# PIC18F57Q84_Curiosity_Nano_Debugger.net
KiCad netlist of a schematic drawn in Altium Designer
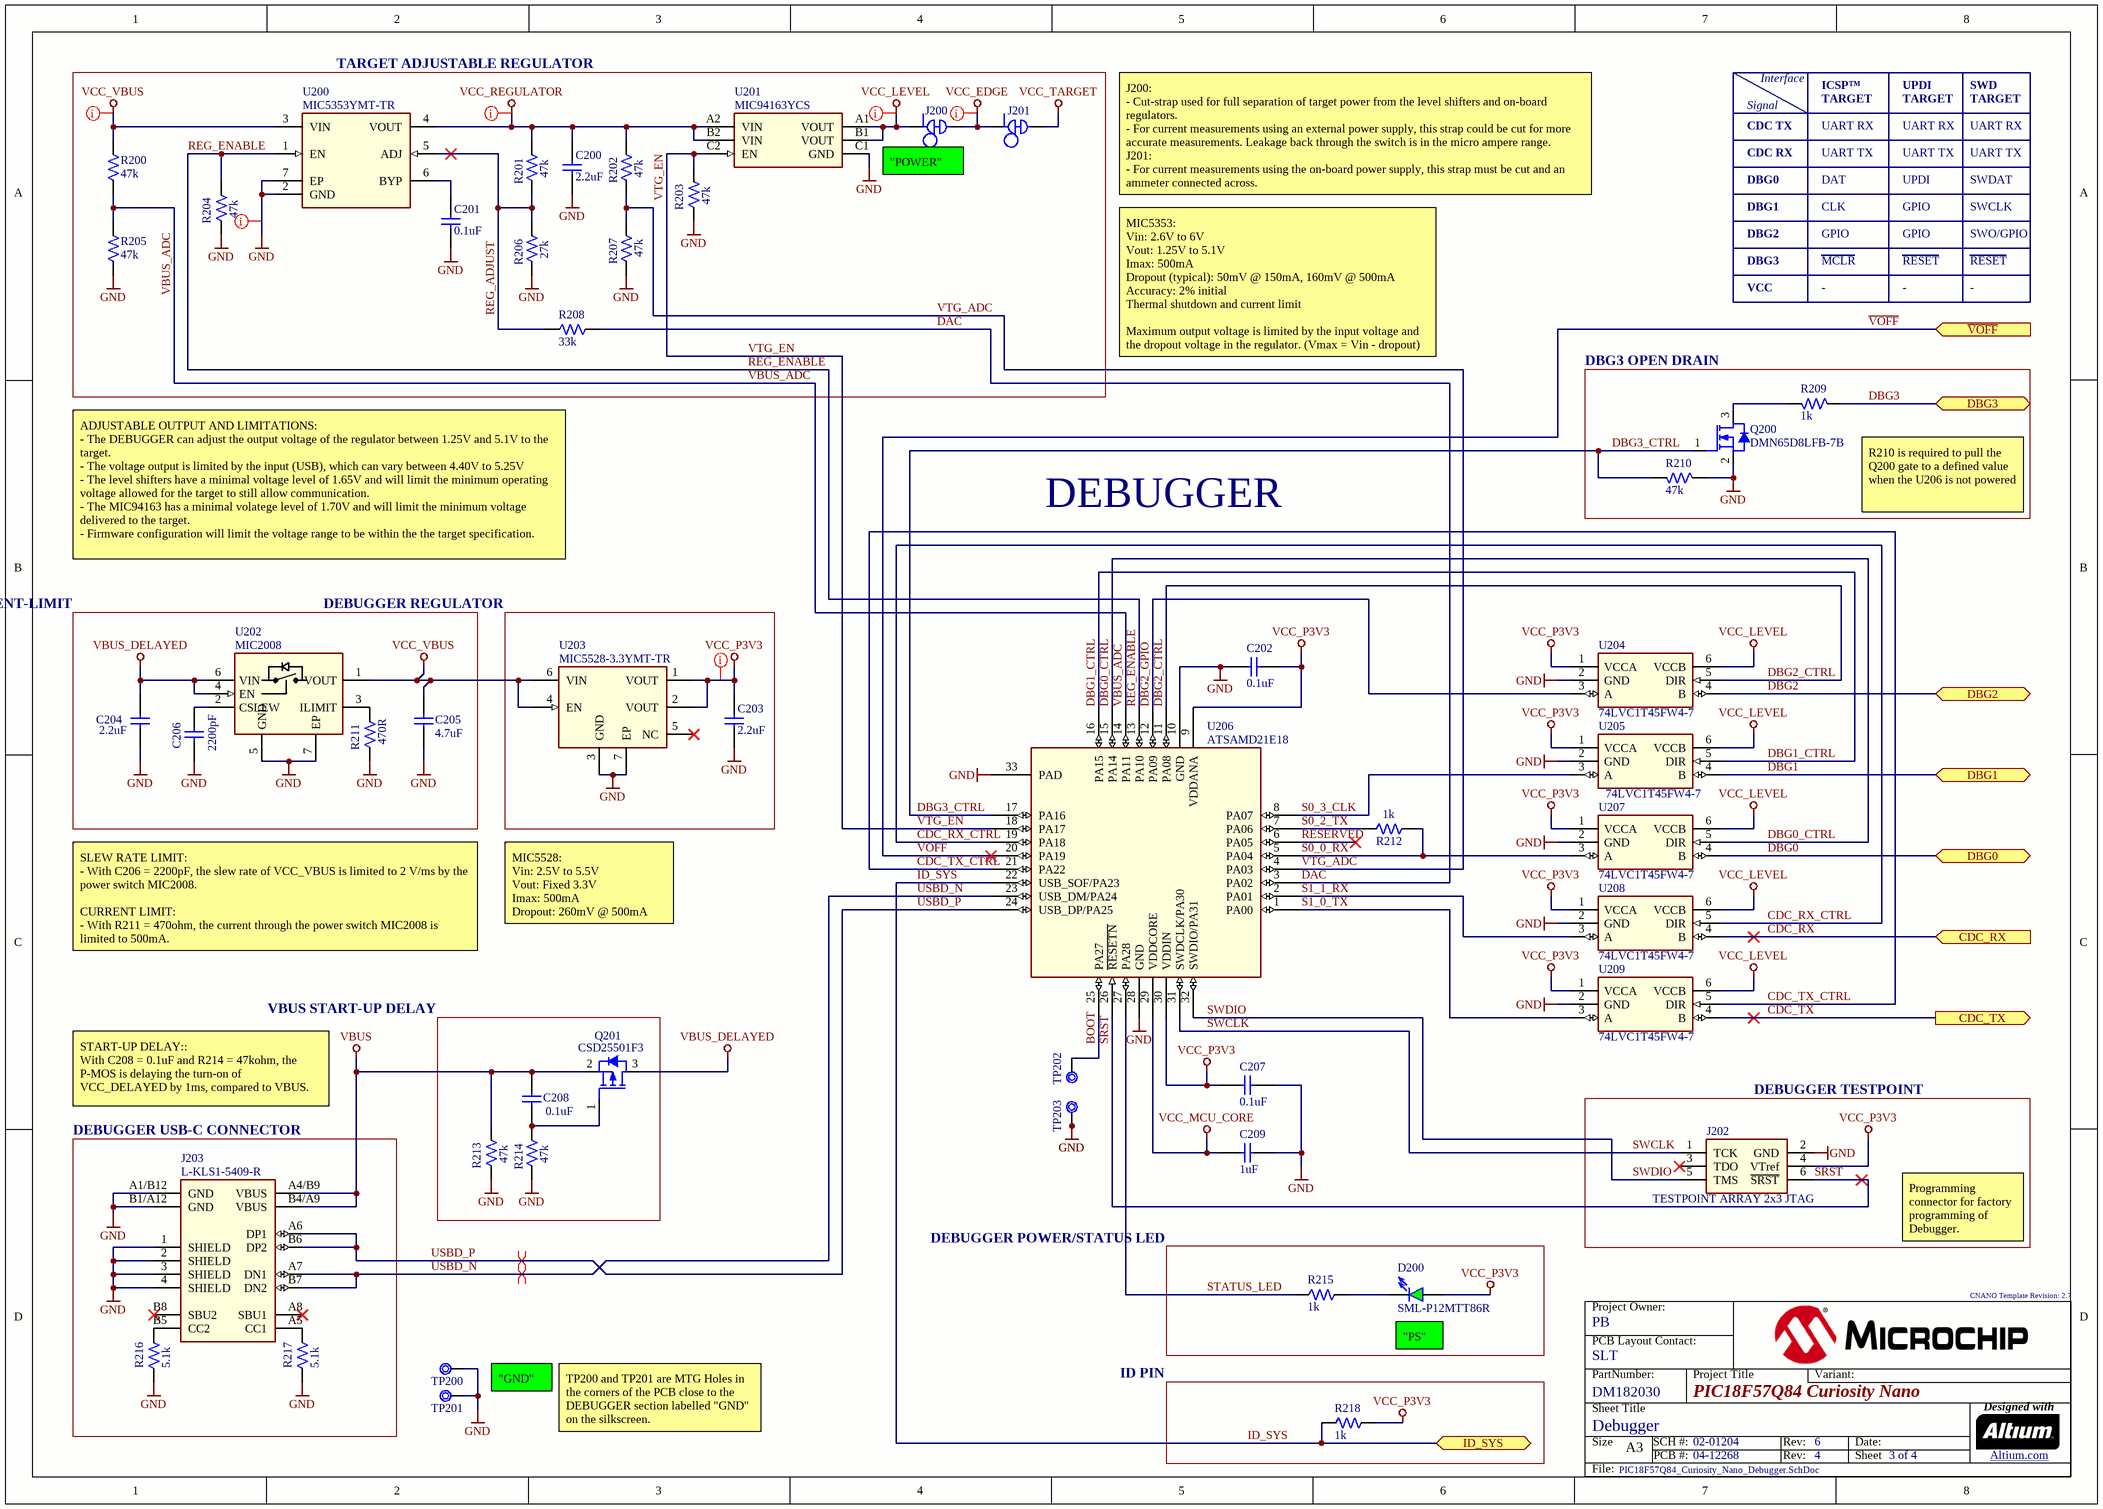
[diagram p0: PIC18F57Q84_Curiosity_Nano_Debugger.SchDoc]

(export (version "E")
  (design (tool "Eeschema 10.0.6"))
  (components
    (comp (ref "C200")
      (value "2.2uF")
      (footprint "CAP_C_0402")
      (fields
        (field (name "VOLTAGE") "10V")
        (field (name "TOLERANCE") "10%")
        (field (name "Comment") "Capacitor NP")
      )
      (libsource (lib "MCHP-CDB") (part "Capacitor NP"))
    )
    (comp (ref "C201")
      (value "0.1uF")
      (footprint "CAP_C_0402")
      (fields
        (field (name "VOLTAGE") "16V")
        (field (name "TOLERANCE") "10%")
        (field (name "Comment") "Capacitor NP")
      )
      (libsource (lib "MCHP-CDB") (part "Capacitor NP"))
    )
    (comp (ref "C202")
      (value "0.1uF")
      (footprint "CAP_C_0402")
      (fields
        (field (name "VOLTAGE") "16V")
        (field (name "TOLERANCE") "10%")
        (field (name "Comment") "Capacitor NP")
      )
      (libsource (lib "MCHP-CDB") (part "Capacitor NP"))
    )
    (comp (ref "C203")
      (value "2.2uF")
      (footprint "CAP_C_0402")
      (fields
        (field (name "VOLTAGE") "10V")
        (field (name "TOLERANCE") "10%")
        (field (name "Comment") "Capacitor NP")
      )
      (libsource (lib "MCHP-CDB") (part "Capacitor NP"))
    )
    (comp (ref "C204")
      (value "2.2uF")
      (footprint "CAP_C_0402")
      (fields
        (field (name "VOLTAGE") "10V")
        (field (name "TOLERANCE") "10%")
        (field (name "Comment") "Capacitor NP")
      )
      (libsource (lib "MCHP-CDB") (part "Capacitor NP"))
    )
    (comp (ref "C205")
      (value "4.7uF")
      (footprint "CAP_C_0603")
      (fields
        (field (name "VOLTAGE") "10V")
        (field (name "TOLERANCE") "10%")
        (field (name "Comment") "Capacitor NP")
      )
      (libsource (lib "MCHP-CDB") (part "Capacitor NP"))
    )
    (comp (ref "C206")
      (value "2200pF")
      (footprint "CAP_C_0402")
      (fields
        (field (name "VOLTAGE") "25V")
        (field (name "TOLERANCE") "5%")
        (field (name "Comment") "Capacitor NP")
      )
      (libsource (lib "MCHP-CDB") (part "Capacitor NP"))
    )
    (comp (ref "C207")
      (value "0.1uF")
      (footprint "CAP_C_0402")
      (fields
        (field (name "VOLTAGE") "16V")
        (field (name "TOLERANCE") "10%")
        (field (name "Comment") "Capacitor NP")
      )
      (libsource (lib "MCHP-CDB") (part "Capacitor NP"))
    )
    (comp (ref "C208")
      (value "0.1uF")
      (footprint "CAP_C_0402")
      (fields
        (field (name "VOLTAGE") "16V")
        (field (name "TOLERANCE") "10%")
        (field (name "Comment") "Capacitor NP")
      )
      (libsource (lib "MCHP-CDB") (part "Capacitor NP"))
    )
    (comp (ref "C209")
      (value "1uF")
      (footprint "CAP_C_0402")
      (fields
        (field (name "VOLTAGE") "6.3V")
        (field (name "TOLERANCE") "10%")
        (field (name "Comment") "Capacitor NP")
      )
      (libsource (lib "MCHP-CDB") (part "Capacitor NP"))
    )
    (comp (ref "D200")
      (value "LED_green")
      (footprint "LED_0402_GREEN")
      (description "LED")
      (fields (field (name "POWER") "54mW") (field (name "MANUFACTURER PART NUMBER 1") "SML-P12MTT86R"))
      (libsource (lib "MCHP-CDB") (part "LED_green"))
    )
    (comp (ref "J200")
      (value "CON JMPR LINK CLOSED")
      (footprint "CON_JMPR_0402_PCB_TRACE_LINK")
      (libsource (lib "MCHP-CDB") (part "CON JMPR LINK CLOSED"))
    )
    (comp (ref "J201")
      (value "CON JMPR LINK CLOSED")
      (footprint "CON_JMPR_2.54_1x2_TH_PCB_TRACE_LINK")
      (libsource (lib "MCHP-CDB") (part "CON JMPR LINK CLOSED"))
    )
    (comp (ref "J202")
      (value "TESTPOINT ARRAY 2x3 JTAG")
      (footprint "TESTPOINT_ARRAY_2x3_1.27mm_pitch_SMD")
      (fields (field (name "Comment") "TP ARRAY NO BOM"))
      (libsource (lib "MCHP-CDB") (part "TESTPOINT ARRAY 2x3 JTAG"))
    )
    (comp (ref "J203")
      (value "CON USB2.0-C RCPT SMD RA KLS KLS1-5409")
      (footprint "CON_USB2.0-C_RCPT_SMD_RA_KLS_KLS1-5409")
      (fields (field (name "VOLTAGE") "100V AC") (field (name "MANUFACTURER PART NUMBER 1") "L-KLS1-5409-R"))
      (libsource (lib "MCHP-CDB") (part "CON USB2.0-C RCPT SMD RA KLS KLS1-5409"))
    )
    (comp (ref "Q200")
      (value "DMN65D8LFB-7B")
      (footprint "X1-DFN1006-3")
      (description "Transistor MOS")
      (fields (field (name "POWER") "430mW") (field (name "VOLTAGE") "60V"))
      (libsource (lib "MCHP-CDB") (part "Transistor MOS-N GSD"))
    )
    (comp (ref "Q201")
      (value "CSD25501F3")
      (footprint "LGA-3_GSD_0.7x0.6_CSD25501F3")
      (description "Transistor MOS")
      (fields (field (name "VOLTAGE") "-20V") (field (name "Comment") "Transistor MOS-P GSD"))
      (libsource (lib "MCHP-CDB") (part "Transistor MOS-P GSD"))
    )
    (comp (ref "R200")
      (value "47k")
      (footprint "RES_C_0402")
      (description "Resistor")
      (fields (field (name "TOLERANCE") "1%") (field (name "VOLTAGE") "50V"))
      (libsource (lib "MCHP-CDB") (part "Resistor"))
    )
    (comp (ref "R201")
      (value "47k")
      (footprint "RES_C_0402")
      (description "Resistor")
      (fields (field (name "TOLERANCE") "1%") (field (name "VOLTAGE") "50V"))
      (libsource (lib "MCHP-CDB") (part "Resistor"))
    )
    (comp (ref "R202")
      (value "47k")
      (footprint "RES_C_0402")
      (description "Resistor")
      (fields (field (name "TOLERANCE") "1%") (field (name "VOLTAGE") "50V"))
      (libsource (lib "MCHP-CDB") (part "Resistor"))
    )
    (comp (ref "R203")
      (value "47k")
      (footprint "RES_C_0402")
      (description "Resistor")
      (fields (field (name "TOLERANCE") "1%") (field (name "VOLTAGE") "50V"))
      (libsource (lib "MCHP-CDB") (part "Resistor"))
    )
    (comp (ref "R204")
      (value "47k")
      (footprint "RES_C_0402")
      (description "Resistor")
      (fields (field (name "TOLERANCE") "1%") (field (name "VOLTAGE") "50V"))
      (libsource (lib "MCHP-CDB") (part "Resistor"))
    )
    (comp (ref "R205")
      (value "47k")
      (footprint "RES_C_0402")
      (description "Resistor")
      (fields (field (name "TOLERANCE") "1%") (field (name "VOLTAGE") "50V"))
      (libsource (lib "MCHP-CDB") (part "Resistor"))
    )
    (comp (ref "R206")
      (value "27k")
      (footprint "RES_C_0402")
      (description "Resistor")
      (fields (field (name "TOLERANCE") "1%") (field (name "VOLTAGE") "50V"))
      (libsource (lib "MCHP-CDB") (part "Resistor"))
    )
    (comp (ref "R207")
      (value "47k")
      (footprint "RES_C_0402")
      (description "Resistor")
      (fields (field (name "TOLERANCE") "1%") (field (name "VOLTAGE") "50V"))
      (libsource (lib "MCHP-CDB") (part "Resistor"))
    )
    (comp (ref "R208")
      (value "33k")
      (footprint "RES_C_0402")
      (description "Resistor")
      (fields (field (name "TOLERANCE") "1%") (field (name "POWER") "1/16W"))
      (libsource (lib "MCHP-CDB") (part "Resistor"))
    )
    (comp (ref "R209")
      (value "1k")
      (footprint "RES_C_0402")
      (description "Resistor")
      (fields (field (name "TOLERANCE") "1%") (field (name "VOLTAGE") "50V"))
      (libsource (lib "MCHP-CDB") (part "Resistor"))
    )
    (comp (ref "R210")
      (value "47k")
      (footprint "RES_C_0402")
      (description "Resistor")
      (fields (field (name "TOLERANCE") "1%") (field (name "VOLTAGE") "50V"))
      (libsource (lib "MCHP-CDB") (part "Resistor"))
    )
    (comp (ref "R211")
      (value "470R")
      (footprint "RES_C_0402")
      (description "Resistor")
      (fields (field (name "TOLERANCE") "1%"))
      (libsource (lib "") (part "Resistor_1"))
    )
    (comp (ref "R212")
      (value "1k")
      (footprint "RES_C_0402")
      (description "Resistor")
      (fields (field (name "TOLERANCE") "1%") (field (name "VOLTAGE") "50V"))
      (libsource (lib "MCHP-CDB") (part "Resistor"))
    )
    (comp (ref "R213")
      (value "47k")
      (footprint "RES_C_0402")
      (description "Resistor")
      (fields (field (name "TOLERANCE") "1%") (field (name "VOLTAGE") "50V"))
      (libsource (lib "MCHP-CDB") (part "Resistor"))
    )
    (comp (ref "R214")
      (value "47k")
      (footprint "RES_C_0402")
      (description "Resistor")
      (fields (field (name "TOLERANCE") "1%") (field (name "VOLTAGE") "50V"))
      (libsource (lib "") (part "Resistor_1"))
    )
    (comp (ref "R215")
      (value "1k")
      (footprint "RES_C_0402")
      (description "Resistor")
      (fields (field (name "TOLERANCE") "1%") (field (name "VOLTAGE") "50V"))
      (libsource (lib "MCHP-CDB") (part "Resistor"))
    )
    (comp (ref "R216")
      (value "5.1k")
      (footprint "RES_C_0402")
      (description "Resistor")
      (fields (field (name "TOLERANCE") "1%") (field (name "POWER") "1/10W"))
      (libsource (lib "") (part "Resistor_1"))
    )
    (comp (ref "R217")
      (value "5.1k")
      (footprint "RES_C_0402")
      (description "Resistor")
      (fields (field (name "TOLERANCE") "1%") (field (name "POWER") "1/10W"))
      (libsource (lib "") (part "Resistor_1"))
    )
    (comp (ref "R218")
      (value "1k")
      (footprint "RES_C_0402")
      (description "Resistor")
      (fields (field (name "TOLERANCE") "1%") (field (name "VOLTAGE") "50V"))
      (libsource (lib "MCHP-CDB") (part "Resistor"))
    )
    (comp (ref "TP200")
      (value "Test Point No BOM")
      (footprint "TP_3.6X2.7")
      (description "Test Point")
      (libsource (lib "MCHP-CDB") (part "Test Point No BOM"))
    )
    (comp (ref "TP201")
      (value "Test Point No BOM")
      (footprint "TP_3.6X2.7")
      (description "Test Point")
      (libsource (lib "MCHP-CDB") (part "Test Point No BOM"))
    )
    (comp (ref "TP202")
      (value "Test Point No BOM")
      (footprint "CON_TP_0.8dia_SMD_with_Test_Jig_Layer")
      (description "Test Point")
      (libsource (lib "MCHP-CDB") (part "Test Point No BOM"))
    )
    (comp (ref "TP203")
      (value "Test Point No BOM")
      (footprint "CON_TP_0.8dia_SMD_with_Test_Jig_Layer")
      (description "Test Point")
      (libsource (lib "MCHP-CDB") (part "Test Point No BOM"))
    )
    (comp (ref "U200")
      (value "MIC5353YMT-TR")
      (footprint "MLF-6 1.6X1.6mm")
      (description "LDO Regulator")
      (fields (field (name "Comment") "MIC53XX ADJ MLF-6"))
      (libsource (lib "MCHP-CDB") (part "MIC53XX ADJ MLF-6"))
    )
    (comp (ref "U201")
      (value "MIC94163YCS")
      (footprint "MIC94163_1.5MM_1MM")
      (fields (field (name "Comment") "MIC94163_1.5MM_1MM"))
      (libsource (lib "MCHP-CDB") (part "MIC94163_1.5MM_1MM"))
    )
    (comp (ref "U202")
      (value "MIC2008")
      (footprint "VDFN-6_2x2_EP0.8X1.40")
      (fields (field (name "Comment") "MIC2008YML-TR VDFN-6"))
      (libsource (lib "MCHP-CDB") (part "MIC2008YML-TR VDFN-6"))
    )
    (comp (ref "U203")
      (value "MIC5528MT DFN-6")
      (footprint "DFN-6_1.2x1.2")
      (fields (field (name "MANUFACTURER PART NUMBER 1") "MIC5528-3.3YMT-TR"))
      (libsource (lib "MCHP-CDB") (part "MIC5528MT DFN-6"))
    )
    (comp (ref "U204")
      (value "74LVC1T45FW4-7")
      (footprint "X2-DFN1010-6")
      (fields (field (name "Comment") "74LVC(H)1T45 SOT-23-6_SC-70-6_SOT-6_SOT-363_DSBGA"))
      (libsource (lib "MCHP-CDB") (part "74LVC(H)1T45 SOT-23-6_SC-70-6_SOT-6_SOT-363_DSBGA"))
    )
    (comp (ref "U205")
      (value "74LVC1T45FW4-7")
      (footprint "X2-DFN1010-6")
      (fields (field (name "Comment") "74LVC(H)1T45 SOT-23-6_SC-70-6_SOT-6_SOT-363_DSBGA"))
      (libsource (lib "MCHP-CDB") (part "74LVC(H)1T45 SOT-23-6_SC-70-6_SOT-6_SOT-363_DSBGA"))
    )
    (comp (ref "U206")
      (value "ATSAMD21E18")
      (footprint "QFN-32_5X5_EP3.6x3.6_L")
      (fields (field (name "Comment") "SAMD21E QFN-32"))
      (libsource (lib "MCHP-CDB") (part "SAMD21E QFN-32"))
    )
    (comp (ref "U207")
      (value "74LVC1T45FW4-7")
      (footprint "X2-DFN1010-6")
      (fields (field (name "Comment") "74LVC(H)1T45 SOT-23-6_SC-70-6_SOT-6_SOT-363_DSBGA"))
      (libsource (lib "MCHP-CDB") (part "74LVC(H)1T45 SOT-23-6_SC-70-6_SOT-6_SOT-363_DSBGA"))
    )
    (comp (ref "U208")
      (value "74LVC1T45FW4-7")
      (footprint "X2-DFN1010-6")
      (fields (field (name "Comment") "74LVC(H)1T45 SOT-23-6_SC-70-6_SOT-6_SOT-363_DSBGA"))
      (libsource (lib "MCHP-CDB") (part "74LVC(H)1T45 SOT-23-6_SC-70-6_SOT-6_SOT-363_DSBGA"))
    )
    (comp (ref "U209")
      (value "74LVC1T45FW4-7")
      (footprint "X2-DFN1010-6")
      (fields (field (name "Comment") "74LVC(H)1T45 SOT-23-6_SC-70-6_SOT-6_SOT-363_DSBGA"))
      (libsource (lib "MCHP-CDB") (part "74LVC(H)1T45 SOT-23-6_SC-70-6_SOT-6_SOT-363_DSBGA"))
    )
  )
  (nets
    (net (code "1") (name "/BOOT") (class "Default")
      (node (ref "TP202") (pin "1") (pinfunction "1_1") (pintype "passive"))
      (node (ref "U206") (pin "25") (pinfunction "PA27_25") (pintype "bidirectional"))
    )
    (net (code "2") (name "/CDC_RX") (class "Default")
      (node (ref "U208") (pin "4") (pinfunction "B_4") (pintype "bidirectional"))
    )
    (net (code "3") (name "/CDC_RX_CTRL") (class "Default")
      (node (ref "U206") (pin "19") (pinfunction "PA18_19") (pintype "bidirectional"))
      (node (ref "U208") (pin "5") (pinfunction "DIR_5") (pintype "input"))
    )
    (net (code "4") (name "/CDC_TX") (class "Default")
      (node (ref "U209") (pin "4") (pinfunction "B_4") (pintype "bidirectional"))
    )
    (net (code "5") (name "/CDC_TX_CTRL") (class "Default")
      (node (ref "U206") (pin "21") (pinfunction "PA22_21") (pintype "bidirectional"))
      (node (ref "U209") (pin "5") (pinfunction "DIR_5") (pintype "input"))
    )
    (net (code "6") (name "/DAC") (class "Default")
      (node (ref "R208") (pin "2") (pinfunction "2_2") (pintype "passive"))
      (node (ref "U206") (pin "3") (pinfunction "PA02_3") (pintype "bidirectional"))
    )
    (net (code "7") (name "/DBG0") (class "Default")
      (node (ref "U207") (pin "4") (pinfunction "B_4") (pintype "bidirectional"))
    )
    (net (code "8") (name "/DBG0_CTRL") (class "Default")
      (node (ref "U206") (pin "15") (pinfunction "PA14_15") (pintype "bidirectional"))
      (node (ref "U207") (pin "5") (pinfunction "DIR_5") (pintype "input"))
    )
    (net (code "9") (name "/DBG1") (class "Default")
      (node (ref "U205") (pin "4") (pinfunction "B_4") (pintype "bidirectional"))
    )
    (net (code "10") (name "/DBG1_CTRL") (class "Default")
      (node (ref "U205") (pin "5") (pinfunction "DIR_5") (pintype "input"))
      (node (ref "U206") (pin "16") (pinfunction "PA15_16") (pintype "bidirectional"))
    )
    (net (code "11") (name "/DBG2") (class "Default")
      (node (ref "U204") (pin "4") (pinfunction "B_4") (pintype "bidirectional"))
    )
    (net (code "12") (name "/DBG2_CTRL") (class "Default")
      (node (ref "U204") (pin "5") (pinfunction "DIR_5") (pintype "input"))
      (node (ref "U206") (pin "11") (pinfunction "PA08_11") (pintype "bidirectional"))
    )
    (net (code "13") (name "/DBG2_GPIO") (class "Default")
      (node (ref "U204") (pin "3") (pinfunction "A_3") (pintype "bidirectional"))
      (node (ref "U206") (pin "12") (pinfunction "PA09_12") (pintype "bidirectional"))
    )
    (net (code "14") (name "/DBG3") (class "Default")
      (node (ref "R209") (pin "2") (pinfunction "2_2") (pintype "passive"))
    )
    (net (code "15") (name "/DBG3_CTRL") (class "Default")
      (node (ref "Q200") (pin "1") (pinfunction "G_1") (pintype "passive"))
      (node (ref "R210") (pin "1") (pinfunction "1_1") (pintype "passive"))
      (node (ref "U206") (pin "17") (pinfunction "PA16_17") (pintype "bidirectional"))
    )
    (net (code "16") (name "/ID_SYS") (class "Default")
      (node (ref "R218") (pin "1") (pinfunction "1_1") (pintype "passive"))
      (node (ref "U206") (pin "22") (pinfunction "USB_SOF/PA23_22") (pintype "bidirectional"))
    )
    (net (code "17") (name "/REG_ADJUST") (class "Default")
      (node (ref "R201") (pin "2") (pinfunction "2_2") (pintype "passive"))
      (node (ref "R206") (pin "2") (pinfunction "2_2") (pintype "passive"))
      (node (ref "R208") (pin "1") (pinfunction "1_1") (pintype "passive"))
      (node (ref "U200") (pin "5") (pinfunction "ADJ_5") (pintype "input"))
    )
    (net (code "18") (name "/REG_ENABLE") (class "Default")
      (node (ref "R204") (pin "1") (pinfunction "1_1") (pintype "passive"))
      (node (ref "U200") (pin "1") (pinfunction "EN_1") (pintype "input"))
      (node (ref "U206") (pin "13") (pinfunction "PA10_13") (pintype "bidirectional"))
    )
    (net (code "19") (name "/RESERVED") (class "Default")
      (node (ref "U206") (pin "6") (pinfunction "PA05_6") (pintype "bidirectional+no_connect"))
    )
    (net (code "20") (name "/S0_0_RX") (class "Default")
      (node (ref "R212") (pin "1") (pinfunction "1_1") (pintype "passive"))
      (node (ref "U206") (pin "5") (pinfunction "PA04_5") (pintype "bidirectional"))
      (node (ref "U207") (pin "3") (pinfunction "A_3") (pintype "bidirectional"))
    )
    (net (code "21") (name "/S0_2_TX") (class "Default")
      (node (ref "R212") (pin "2") (pinfunction "2_2") (pintype "passive"))
      (node (ref "U206") (pin "7") (pinfunction "PA06_7") (pintype "bidirectional"))
    )
    (net (code "22") (name "/S0_3_CLK") (class "Default")
      (node (ref "U205") (pin "3") (pinfunction "A_3") (pintype "bidirectional"))
      (node (ref "U206") (pin "8") (pinfunction "PA07_8") (pintype "bidirectional"))
    )
    (net (code "23") (name "/S1_0_TX") (class "Default")
      (node (ref "U206") (pin "1") (pinfunction "PA00_1") (pintype "bidirectional"))
      (node (ref "U209") (pin "3") (pinfunction "A_3") (pintype "bidirectional"))
    )
    (net (code "24") (name "/S1_1_RX") (class "Default")
      (node (ref "U206") (pin "2") (pinfunction "PA01_2") (pintype "bidirectional"))
      (node (ref "U208") (pin "3") (pinfunction "A_3") (pintype "bidirectional"))
    )
    (net (code "25") (name "/STATUS_LED") (class "Default")
      (node (ref "R215") (pin "2") (pinfunction "2_2") (pintype "passive"))
      (node (ref "U206") (pin "27") (pinfunction "PA28_27") (pintype "bidirectional"))
    )
    (net (code "26") (name "/SWCLK") (class "Default")
      (node (ref "J202") (pin "1") (pinfunction "TCK_1") (pintype "passive"))
      (node (ref "U206") (pin "31") (pinfunction "SWDCLK/PA30_31") (pintype "bidirectional"))
    )
    (net (code "27") (name "/SWDIO") (class "Default")
      (node (ref "J202") (pin "5") (pinfunction "TMS_5") (pintype "passive"))
      (node (ref "U206") (pin "32") (pinfunction "SWDIO/PA31_32") (pintype "bidirectional"))
    )
    (net (code "28") (name "/USBD_N") (class "Default")
      (node (ref "J203") (pin "A7") (pinfunction "DN1_A7") (pintype "bidirectional"))
      (node (ref "J203") (pin "B7") (pinfunction "DN2_B7") (pintype "bidirectional"))
      (node (ref "U206") (pin "23") (pinfunction "USB_DM/PA24_23") (pintype "bidirectional"))
    )
    (net (code "29") (name "/USBD_P") (class "Default")
      (node (ref "J203") (pin "A6") (pinfunction "DP1_A6") (pintype "bidirectional"))
      (node (ref "J203") (pin "B6") (pinfunction "DP2_B6") (pintype "bidirectional"))
      (node (ref "U206") (pin "24") (pinfunction "USB_DP/PA25_24") (pintype "bidirectional"))
    )
    (net (code "30") (name "/VBUS_ADC") (class "Default")
      (node (ref "R200") (pin "2") (pinfunction "2_2") (pintype "passive"))
      (node (ref "R205") (pin "2") (pinfunction "2_2") (pintype "passive"))
      (node (ref "U206") (pin "14") (pinfunction "PA11_14") (pintype "bidirectional"))
    )
    (net (code "31") (name "/VTG_ADC") (class "Default")
      (node (ref "R202") (pin "1") (pinfunction "1_1") (pintype "passive"))
      (node (ref "R207") (pin "2") (pinfunction "2_2") (pintype "passive"))
      (node (ref "U206") (pin "4") (pinfunction "PA03_4") (pintype "bidirectional"))
    )
    (net (code "32") (name "/VTG_EN") (class "Default")
      (node (ref "R203") (pin "1") (pinfunction "1_1") (pintype "passive"))
      (node (ref "U201") (pin "C2") (pinfunction "EN_C2") (pintype "input"))
      (node (ref "U206") (pin "18") (pinfunction "PA17_18") (pintype "bidirectional"))
    )
    (net (code "33") (name "/~{SRST}") (class "Default")
      (node (ref "J202") (pin "6") (pinfunction "~{SRST}_6") (pintype "passive"))
      (node (ref "U206") (pin "26") (pinfunction "~{RESETN}_26") (pintype "input"))
    )
    (net (code "34") (name "/~{VOFF}") (class "Default")
      (node (ref "U206") (pin "20") (pinfunction "PA19_20") (pintype "bidirectional+no_connect"))
    )
    (net (code "35") (name "GND") (class "Default")
      (node (ref "C200") (pin "1") (pinfunction "1_1") (pintype "passive"))
      (node (ref "C201") (pin "2") (pinfunction "2_2") (pintype "passive"))
      (node (ref "C202") (pin "1") (pinfunction "1_1") (pintype "passive"))
      (node (ref "C203") (pin "1") (pinfunction "1_1") (pintype "passive"))
      (node (ref "C204") (pin "1") (pinfunction "1_1") (pintype "passive"))
      (node (ref "C205") (pin "1") (pinfunction "1_1") (pintype "passive"))
      (node (ref "C206") (pin "1") (pinfunction "1_1") (pintype "passive"))
      (node (ref "C207") (pin "2") (pinfunction "2_2") (pintype "passive"))
      (node (ref "C209") (pin "1") (pinfunction "1_1") (pintype "passive"))
      (node (ref "J202") (pin "2") (pinfunction "GND_2") (pintype "power_in"))
      (node (ref "J203") (pin "1") (pinfunction "SHIELD_1") (pintype "passive"))
      (node (ref "J203") (pin "2") (pinfunction "SHIELD_2") (pintype "passive"))
      (node (ref "J203") (pin "3") (pinfunction "SHIELD_3") (pintype "passive"))
      (node (ref "J203") (pin "4") (pinfunction "SHIELD_4") (pintype "passive"))
      (node (ref "J203") (pin "A1/B12") (pinfunction "GND_A1/B12") (pintype "power_in"))
      (node (ref "J203") (pin "B1/A12") (pinfunction "GND_B1/A12") (pintype "power_in"))
      (node (ref "Q200") (pin "2") (pinfunction "S_2") (pintype "passive"))
      (node (ref "R203") (pin "2") (pinfunction "2_2") (pintype "passive"))
      (node (ref "R204") (pin "2") (pinfunction "2_2") (pintype "passive"))
      (node (ref "R205") (pin "1") (pinfunction "1_1") (pintype "passive"))
      (node (ref "R206") (pin "1") (pinfunction "1_1") (pintype "passive"))
      (node (ref "R207") (pin "1") (pinfunction "1_1") (pintype "passive"))
      (node (ref "R210") (pin "2") (pinfunction "2_2") (pintype "passive"))
      (node (ref "R211") (pin "2") (pinfunction "2_2") (pintype "passive"))
      (node (ref "R213") (pin "2") (pinfunction "2_2") (pintype "passive"))
      (node (ref "R214") (pin "2") (pinfunction "2_2") (pintype "passive"))
      (node (ref "R216") (pin "2") (pinfunction "2_2") (pintype "passive"))
      (node (ref "R217") (pin "2") (pinfunction "2_2") (pintype "passive"))
      (node (ref "TP200") (pin "1") (pinfunction "1_1") (pintype "passive"))
      (node (ref "TP201") (pin "1") (pinfunction "1_1") (pintype "passive"))
      (node (ref "TP203") (pin "1") (pinfunction "1_1") (pintype "passive"))
      (node (ref "U200") (pin "2") (pinfunction "GND_2") (pintype "power_in"))
      (node (ref "U200") (pin "7") (pinfunction "EP_7") (pintype "passive"))
      (node (ref "U201") (pin "C1") (pinfunction "GND_C1") (pintype "passive"))
      (node (ref "U202") (pin "5") (pinfunction "GND_5") (pintype "power_in"))
      (node (ref "U202") (pin "7") (pinfunction "EP_7") (pintype "power_in"))
      (node (ref "U203") (pin "3") (pinfunction "GND_3") (pintype "power_in"))
      (node (ref "U203") (pin "7") (pinfunction "EP_7") (pintype "passive"))
      (node (ref "U204") (pin "2") (pinfunction "GND_2") (pintype "power_in"))
      (node (ref "U205") (pin "2") (pinfunction "GND_2") (pintype "power_in"))
      (node (ref "U206") (pin "10") (pinfunction "GND_10") (pintype "power_in"))
      (node (ref "U206") (pin "28") (pinfunction "GND_28") (pintype "power_in"))
      (node (ref "U206") (pin "33") (pinfunction "PAD_33") (pintype "passive"))
      (node (ref "U207") (pin "2") (pinfunction "GND_2") (pintype "power_in"))
      (node (ref "U208") (pin "2") (pinfunction "GND_2") (pintype "power_in"))
      (node (ref "U209") (pin "2") (pinfunction "GND_2") (pintype "power_in"))
    )
    (net (code "36") (name "Net-(D200-K)") (class "Default")
      (node (ref "D200") (pin "2") (pinfunction "K_2") (pintype "passive"))
      (node (ref "R215") (pin "1") (pinfunction "1_1") (pintype "passive"))
    )
    (net (code "37") (name "Net-(J203-CC1)") (class "Default")
      (node (ref "J203") (pin "A5") (pinfunction "CC1_A5") (pintype "passive"))
      (node (ref "R217") (pin "1") (pinfunction "1_1") (pintype "passive"))
    )
    (net (code "38") (name "Net-(J203-CC2)") (class "Default")
      (node (ref "J203") (pin "B5") (pinfunction "CC2_B5") (pintype "passive"))
      (node (ref "R216") (pin "1") (pinfunction "1_1") (pintype "passive"))
    )
    (net (code "39") (name "Net-(Q200-D)") (class "Default")
      (node (ref "Q200") (pin "3") (pinfunction "D_3") (pintype "passive"))
      (node (ref "R209") (pin "1") (pinfunction "1_1") (pintype "passive"))
    )
    (net (code "40") (name "Net-(Q201-G)") (class "Default")
      (node (ref "C208") (pin "1") (pinfunction "1_1") (pintype "passive"))
      (node (ref "Q201") (pin "1") (pinfunction "G_1") (pintype "passive"))
      (node (ref "R214") (pin "1") (pinfunction "1_1") (pintype "passive"))
    )
    (net (code "41") (name "Net-(U200-BYP)") (class "Default")
      (node (ref "C201") (pin "1") (pinfunction "1_1") (pintype "passive"))
      (node (ref "U200") (pin "6") (pinfunction "BYP_6") (pintype "power_in"))
    )
    (net (code "42") (name "Net-(U202-CSLEW)") (class "Default")
      (node (ref "C206") (pin "2") (pinfunction "2_2") (pintype "passive"))
      (node (ref "U202") (pin "2") (pinfunction "CSLEW_2") (pintype "passive"))
    )
    (net (code "43") (name "Net-(U202-ILIMIT)") (class "Default")
      (node (ref "R211") (pin "1") (pinfunction "1_1") (pintype "passive"))
      (node (ref "U202") (pin "3") (pinfunction "ILIMIT_3") (pintype "passive"))
    )
    (net (code "44") (name "VBUS") (class "Default")
      (node (ref "C208") (pin "2") (pinfunction "2_2") (pintype "passive"))
      (node (ref "J203") (pin "A4/B9") (pinfunction "VBUS_A4/B9") (pintype "power_in"))
      (node (ref "J203") (pin "B4/A9") (pinfunction "VBUS_B4/A9") (pintype "power_in"))
      (node (ref "Q201") (pin "2") (pinfunction "S_2") (pintype "passive"))
      (node (ref "R213") (pin "1") (pinfunction "1_1") (pintype "passive"))
    )
    (net (code "45") (name "VBUS_DELAYED") (class "Default")
      (node (ref "C204") (pin "2") (pinfunction "2_2") (pintype "passive"))
      (node (ref "Q201") (pin "3") (pinfunction "D_3") (pintype "passive"))
      (node (ref "U202") (pin "4") (pinfunction "EN_4") (pintype "input"))
      (node (ref "U202") (pin "6") (pinfunction "VIN_6") (pintype "power_in"))
    )
    (net (code "46") (name "VCC_EDGE") (class "Default")
      (node (ref "J200") (pin "2") (pinfunction "2_2") (pintype "passive"))
      (node (ref "J201") (pin "1") (pinfunction "1_1") (pintype "passive"))
    )
    (net (code "47") (name "VCC_LEVEL") (class "Default")
      (node (ref "J200") (pin "1") (pinfunction "1_1") (pintype "passive"))
      (node (ref "U201") (pin "A1") (pinfunction "VOUT_A1") (pintype "passive"))
      (node (ref "U201") (pin "B1") (pinfunction "VOUT_B1") (pintype "passive"))
      (node (ref "U204") (pin "6") (pinfunction "VCCB_6") (pintype "power_in"))
      (node (ref "U205") (pin "6") (pinfunction "VCCB_6") (pintype "power_in"))
      (node (ref "U207") (pin "6") (pinfunction "VCCB_6") (pintype "power_in"))
      (node (ref "U208") (pin "6") (pinfunction "VCCB_6") (pintype "power_in"))
      (node (ref "U209") (pin "6") (pinfunction "VCCB_6") (pintype "power_in"))
    )
    (net (code "48") (name "VCC_MCU_CORE") (class "Default")
      (node (ref "C209") (pin "2") (pinfunction "2_2") (pintype "passive"))
      (node (ref "U206") (pin "29") (pinfunction "VDDCORE_29") (pintype "power_in"))
    )
    (net (code "49") (name "VCC_P3V3") (class "Default")
      (node (ref "C202") (pin "2") (pinfunction "2_2") (pintype "passive"))
      (node (ref "C203") (pin "2") (pinfunction "2_2") (pintype "passive"))
      (node (ref "C207") (pin "1") (pinfunction "1_1") (pintype "passive"))
      (node (ref "D200") (pin "1") (pinfunction "A_1") (pintype "passive"))
      (node (ref "J202") (pin "4") (pinfunction "VTref_4") (pintype "passive"))
      (node (ref "R218") (pin "2") (pinfunction "2_2") (pintype "passive"))
      (node (ref "U203") (pin "1") (pinfunction "VOUT_1") (pintype "power_in"))
      (node (ref "U203") (pin "2") (pinfunction "VOUT_2") (pintype "power_in"))
      (node (ref "U204") (pin "1") (pinfunction "VCCA_1") (pintype "power_in"))
      (node (ref "U205") (pin "1") (pinfunction "VCCA_1") (pintype "power_in"))
      (node (ref "U206") (pin "30") (pinfunction "VDDIN_30") (pintype "power_in"))
      (node (ref "U206") (pin "9") (pinfunction "VDDANA_9") (pintype "power_in"))
      (node (ref "U207") (pin "1") (pinfunction "VCCA_1") (pintype "power_in"))
      (node (ref "U208") (pin "1") (pinfunction "VCCA_1") (pintype "power_in"))
      (node (ref "U209") (pin "1") (pinfunction "VCCA_1") (pintype "power_in"))
    )
    (net (code "50") (name "VCC_REGULATOR") (class "Default")
      (node (ref "C200") (pin "2") (pinfunction "2_2") (pintype "passive"))
      (node (ref "R201") (pin "1") (pinfunction "1_1") (pintype "passive"))
      (node (ref "R202") (pin "2") (pinfunction "2_2") (pintype "passive"))
      (node (ref "U200") (pin "4") (pinfunction "VOUT_4") (pintype "power_in"))
      (node (ref "U201") (pin "A2") (pinfunction "VIN_A2") (pintype "passive"))
      (node (ref "U201") (pin "B2") (pinfunction "VIN_B2") (pintype "passive"))
    )
    (net (code "51") (name "VCC_TARGET") (class "Default")
      (node (ref "J201") (pin "2") (pinfunction "2_2") (pintype "passive"))
    )
    (net (code "52") (name "VCC_VBUS") (class "Default")
      (node (ref "C205") (pin "2") (pinfunction "2_2") (pintype "passive"))
      (node (ref "R200") (pin "1") (pinfunction "1_1") (pintype "passive"))
      (node (ref "U200") (pin "3") (pinfunction "VIN_3") (pintype "power_in"))
      (node (ref "U202") (pin "1") (pinfunction "VOUT_1") (pintype "power_in"))
      (node (ref "U203") (pin "4") (pinfunction "EN_4") (pintype "input"))
      (node (ref "U203") (pin "6") (pinfunction "VIN_6") (pintype "power_in"))
    )
    (net (code "53") (name "unconnected-(J202-TDO-Pad3)") (class "Default")
      (node (ref "J202") (pin "3") (pinfunction "TDO_3") (pintype "passive+no_connect"))
    )
    (net (code "54") (name "unconnected-(J203-SBU1-PadA8)") (class "Default")
      (node (ref "J203") (pin "A8") (pinfunction "SBU1_A8") (pintype "passive+no_connect"))
    )
    (net (code "55") (name "unconnected-(J203-SBU2-PadB8)") (class "Default")
      (node (ref "J203") (pin "B8") (pinfunction "SBU2_B8") (pintype "passive+no_connect"))
    )
    (net (code "56") (name "unconnected-(U203-NC-Pad5)") (class "Default")
      (node (ref "U203") (pin "5") (pinfunction "NC_5") (pintype "passive+no_connect"))
    )
  )
)
